# Schematic1.net
KiCad netlist of a schematic drawn in EasyEDA Pro
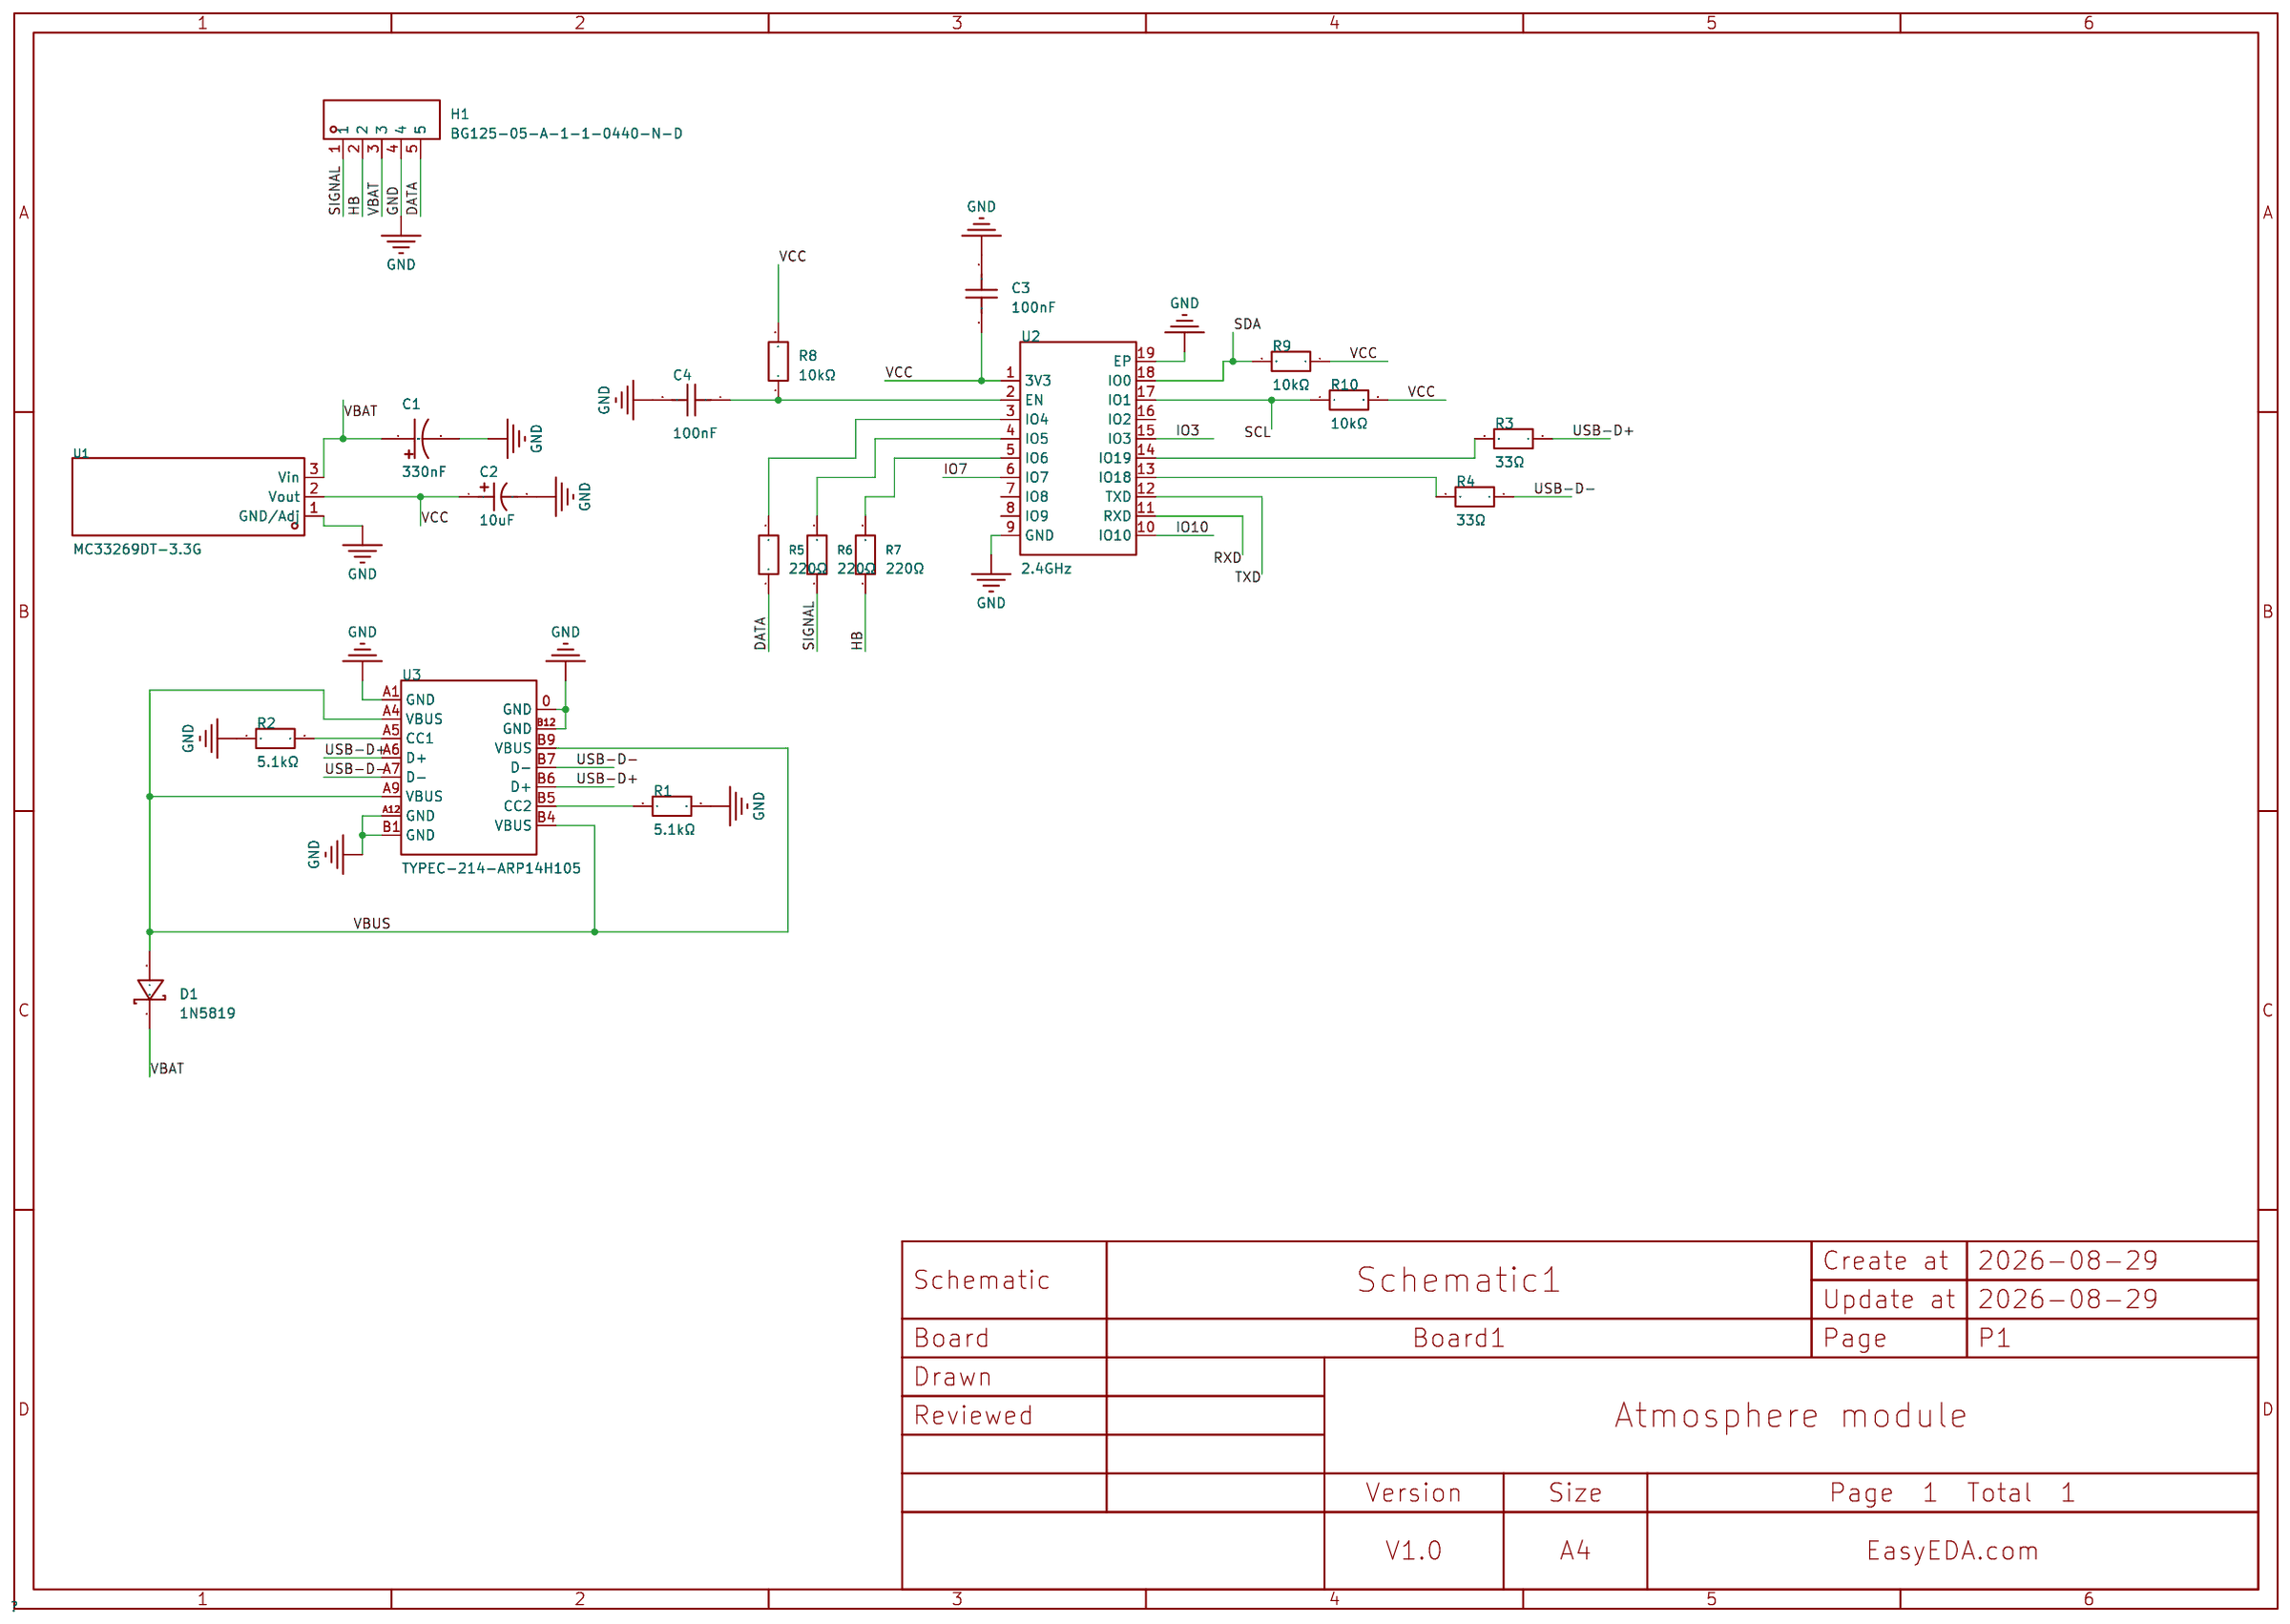
[diagram p0: schematic sheet]

(export (version "E")
  (design (tool "Eeschema 10.0.6"))
  (components
    (comp (ref "C1")
      (value "330nF")
      (footprint "easyedapro:CAP-SMD_L3.2-W1.6")
      (fields (field (name "Manufacturer Part") "T491A334K035AT") (field (name "Manufacturer") "KEMET(基美)"))
      (libsource (lib "easyedapro") (part "T491A334K035AT"))
    )
    (comp (ref "C2")
      (value "10uF")
      (footprint "easyedapro:CASE-A_3216")
      (fields
        (field (name "Manufacturer Part") "T491A106K010AT")
        (field (name "Manufacturer") "KEMET(基美)")
        (field (name "Tolerance") "±10%")
      )
      (libsource (lib "easyedapro") (part "T491A106K010AT_C1508940"))
    )
    (comp (ref "C3")
      (value "100nF")
      (footprint "easyedapro:C0805")
      (fields
        (field (name "Manufacturer Part") "GRM21B7U1A104JA01L")
        (field (name "Manufacturer") "muRata(村田)")
        (field (name "Tolerance") "±5%")
      )
      (libsource (lib "easyedapro") (part "GRM21B7U1A104JA01L"))
    )
    (comp (ref "C4")
      (value "100nF")
      (footprint "easyedapro:C0805")
      (fields
        (field (name "Manufacturer Part") "GRM21B7U1A104JA01L")
        (field (name "Manufacturer") "muRata(村田)")
      )
      (libsource (lib "easyedapro") (part "GRM21B7U1A104JA01L"))
    )
    (comp (ref "D1")
      (value "1N5819")
      (footprint "easyedapro:SMA_L4.4-W2.6-LS5.0-RD")
      (fields (field (name "Manufacturer") "KEXIN(科信)"))
      (libsource (lib "easyedapro") (part "1N5819_C437199"))
    )
    (comp (ref "H1")
      (value "BG125-05-A-1-1-0440-N-D")
      (footprint "easyedapro:HDR-SMD_5P-P2.54-V-F-LS4.4")
      (fields (field (name "Manufacturer") "GCT"))
      (libsource (lib "easyedapro") (part "BG125-05-A-1-1-0440-N-D"))
    )
    (comp (ref "R1")
      (value "5.1kΩ")
      (footprint "easyedapro:R0805")
      (fields
        (field (name "Manufacturer Part") "ERA6AEB512V")
        (field (name "Manufacturer") "PANASONIC(松下)")
        (field (name "Tolerance") "±0.1%")
      )
      (libsource (lib "easyedapro") (part "ERA6AEB512V"))
    )
    (comp (ref "R2")
      (value "5.1kΩ")
      (footprint "easyedapro:R0805")
      (fields
        (field (name "Manufacturer Part") "ERA6AEB512V")
        (field (name "Manufacturer") "PANASONIC(松下)")
        (field (name "Tolerance") "±0.1%")
      )
      (libsource (lib "easyedapro") (part "ERA6AEB512V"))
    )
    (comp (ref "R3")
      (value "33Ω")
      (footprint "easyedapro:R0805")
      (fields
        (field (name "Manufacturer Part") "ERJ6ENF33R0V")
        (field (name "Manufacturer") "PANASONIC(松下)")
        (field (name "Tolerance") "±1%")
      )
      (libsource (lib "easyedapro") (part "ERJ6ENF33R0V"))
    )
    (comp (ref "R4")
      (value "33Ω")
      (footprint "easyedapro:R0805")
      (fields
        (field (name "Manufacturer Part") "ERJ6ENF33R0V")
        (field (name "Manufacturer") "PANASONIC(松下)")
        (field (name "Tolerance") "±1%")
      )
      (libsource (lib "easyedapro") (part "ERJ6ENF33R0V"))
    )
    (comp (ref "R5")
      (value "220Ω")
      (footprint "easyedapro:R0805")
      (fields (field (name "Manufacturer Part") "ERA6AEB221V") (field (name "Manufacturer") "PANASONIC(松下)"))
      (libsource (lib "easyedapro") (part "ERA6AEB221V"))
    )
    (comp (ref "R6")
      (value "220Ω")
      (footprint "easyedapro:R0805")
      (fields (field (name "Manufacturer Part") "ERA6AEB221V") (field (name "Manufacturer") "PANASONIC(松下)"))
      (libsource (lib "easyedapro") (part "ERA6AEB221V"))
    )
    (comp (ref "R7")
      (value "220Ω")
      (footprint "easyedapro:R0805")
      (fields (field (name "Manufacturer Part") "ERA6AEB221V") (field (name "Manufacturer") "PANASONIC(松下)"))
      (libsource (lib "easyedapro") (part "ERA6AEB221V"))
    )
    (comp (ref "R8")
      (value "10kΩ")
      (footprint "easyedapro:R0805")
      (fields (field (name "Manufacturer Part") "ERJP06F1002V") (field (name "Manufacturer") "PANASONIC(松下)"))
      (libsource (lib "easyedapro") (part "ERJP06F1002V"))
    )
    (comp (ref "R9")
      (value "10kΩ")
      (footprint "easyedapro:R0805")
      (fields (field (name "Manufacturer Part") "ERJP06F1002V") (field (name "Manufacturer") "PANASONIC(松下)"))
      (libsource (lib "easyedapro") (part "ERJP06F1002V"))
    )
    (comp (ref "R10")
      (value "10kΩ")
      (footprint "easyedapro:R0805")
      (fields (field (name "Manufacturer Part") "ERJP06F1002V") (field (name "Manufacturer") "PANASONIC(松下)"))
      (libsource (lib "easyedapro") (part "ERJP06F1002V"))
    )
    (comp (ref "U1")
      (value "MC33269DT-3.3G")
      (footprint "easyedapro:TO-252-2_L6.6-W6.1-P4.57-LS9.9-BR-CW")
      (fields (field (name "Manufacturer") "onsemi(安森美)"))
      (libsource (lib "easyedapro") (part "MC33269DT-3.3G"))
    )
    (comp (ref "U2")
      (value "2.4GHz")
      (footprint "easyedapro:BULETM-SMD_ESPRESSIF_ESP32-C3-WROOM-02-N4-4MB")
      (fields
        (field (name "Manufacturer Part") "ESP32-C3-WROOM-02-N4")
        (field (name "Manufacturer") "ESPRESSIF(乐鑫)")
      )
      (libsource (lib "easyedapro") (part "ESP32-C3-WROOM-02-N4(4MB)"))
    )
    (comp (ref "U3")
      (value "TYPEC-214-ARP14H105")
      (footprint "easyedapro:USB-TYPE-C-TH_TYPEC-214-ARP14H105")
      (fields (field (name "Manufacturer") "XUNPU(讯普)"))
      (libsource (lib "easyedapro") (part "TYPEC-214-ARP14H105"))
    )
  )
  (nets
    (net (code "1") (name "/DATA") (class "Default")
      (node (ref "H1") (pin "5") (pinfunction "5_5") (pintype "unspecified"))
      (node (ref "R5") (pin "1") (pinfunction "1_1") (pintype "input"))
    )
    (net (code "2") (name "/HB") (class "Default")
      (node (ref "H1") (pin "2") (pinfunction "2_2") (pintype "unspecified"))
      (node (ref "R7") (pin "1") (pinfunction "1_1") (pintype "input"))
    )
    (net (code "3") (name "/IO3") (class "Default")
      (node (ref "U2") (pin "15") (pinfunction "IO3_15") (pintype "unspecified"))
    )
    (net (code "4") (name "/IO7") (class "Default")
      (node (ref "U2") (pin "6") (pinfunction "IO7_6") (pintype "unspecified"))
    )
    (net (code "5") (name "/IO10") (class "Default")
      (node (ref "U2") (pin "10") (pinfunction "IO10_10") (pintype "unspecified"))
    )
    (net (code "6") (name "/RXD") (class "Default")
      (node (ref "U2") (pin "11") (pinfunction "RXD_11") (pintype "unspecified"))
    )
    (net (code "7") (name "/SCL") (class "Default")
      (node (ref "R10") (pin "1") (pinfunction "1_1") (pintype "unspecified"))
      (node (ref "U2") (pin "17") (pinfunction "IO1_17") (pintype "unspecified"))
    )
    (net (code "8") (name "/SDA") (class "Default")
      (node (ref "R9") (pin "2") (pinfunction "2_2") (pintype "unspecified"))
      (node (ref "U2") (pin "18") (pinfunction "IO0_18") (pintype "unspecified"))
    )
    (net (code "9") (name "/SIGNAL") (class "Default")
      (node (ref "H1") (pin "1") (pinfunction "1_1") (pintype "unspecified"))
      (node (ref "R6") (pin "1") (pinfunction "1_1") (pintype "input"))
    )
    (net (code "10") (name "/TXD") (class "Default")
      (node (ref "U2") (pin "12") (pinfunction "TXD_12") (pintype "unspecified"))
    )
    (net (code "11") (name "/USB-D+") (class "Default")
      (node (ref "R3") (pin "1") (pinfunction "1_1") (pintype "unspecified"))
      (node (ref "U3") (pin "A6") (pinfunction "D+_A6") (pintype "unspecified"))
      (node (ref "U3") (pin "B6") (pinfunction "D+_B6") (pintype "unspecified"))
    )
    (net (code "12") (name "/USB-D-") (class "Default")
      (node (ref "R4") (pin "1") (pinfunction "1_1") (pintype "unspecified"))
      (node (ref "U3") (pin "A7") (pinfunction "D-_A7") (pintype "unspecified"))
      (node (ref "U3") (pin "B7") (pinfunction "D-_B7") (pintype "unspecified"))
    )
    (net (code "13") (name "/VBAT") (class "Default")
      (node (ref "C1") (pin "1") (pinfunction "1_1") (pintype "unspecified"))
      (node (ref "D1") (pin "1") (pinfunction "C_1") (pintype "unspecified"))
      (node (ref "H1") (pin "3") (pinfunction "3_3") (pintype "unspecified"))
      (node (ref "U1") (pin "3") (pinfunction "Vin_3") (pintype "input"))
    )
    (net (code "14") (name "/VBUS") (class "Default")
      (node (ref "D1") (pin "2") (pinfunction "A_2") (pintype "unspecified"))
      (node (ref "U3") (pin "A4") (pinfunction "VBUS_A4") (pintype "unspecified"))
      (node (ref "U3") (pin "A9") (pinfunction "VBUS_A9") (pintype "unspecified"))
      (node (ref "U3") (pin "B4") (pinfunction "VBUS_B4") (pintype "unspecified"))
      (node (ref "U3") (pin "B9") (pinfunction "VBUS_B9") (pintype "unspecified"))
    )
    (net (code "15") (name "/VCC") (class "Default")
      (node (ref "C2") (pin "1") (pinfunction "1_1") (pintype "input"))
      (node (ref "C3") (pin "2") (pinfunction "2_2") (pintype "input"))
      (node (ref "R10") (pin "2") (pinfunction "2_2") (pintype "unspecified"))
      (node (ref "R8") (pin "2") (pinfunction "2_2") (pintype "unspecified"))
      (node (ref "R9") (pin "1") (pinfunction "1_1") (pintype "unspecified"))
      (node (ref "U1") (pin "2") (pinfunction "Vout_2") (pintype "input"))
      (node (ref "U2") (pin "1") (pinfunction "3V3_1") (pintype "unspecified"))
    )
    (net (code "16") (name "GND") (class "Default")
      (node (ref "C1") (pin "2") (pinfunction "2_2") (pintype "unspecified"))
      (node (ref "C2") (pin "2") (pinfunction "2_2") (pintype "input"))
      (node (ref "C3") (pin "1") (pinfunction "1_1") (pintype "input"))
      (node (ref "C4") (pin "2") (pinfunction "2_2") (pintype "input"))
      (node (ref "H1") (pin "4") (pinfunction "4_4") (pintype "unspecified"))
      (node (ref "R1") (pin "2") (pinfunction "2_2") (pintype "unspecified"))
      (node (ref "R2") (pin "1") (pinfunction "1_1") (pintype "unspecified"))
      (node (ref "U1") (pin "1") (pinfunction "GND/Adj_1") (pintype "input"))
      (node (ref "U2") (pin "19") (pinfunction "EP_19") (pintype "unspecified"))
      (node (ref "U2") (pin "9") (pinfunction "GND_9") (pintype "unspecified"))
      (node (ref "U3") (pin "0") (pinfunction "GND_0") (pintype "unspecified"))
      (node (ref "U3") (pin "A1") (pinfunction "GND_A1") (pintype "unspecified"))
      (node (ref "U3") (pin "A12") (pinfunction "GND_A12") (pintype "unspecified"))
      (node (ref "U3") (pin "B1") (pinfunction "GND_B1") (pintype "unspecified"))
      (node (ref "U3") (pin "B12") (pinfunction "GND_B12") (pintype "unspecified"))
    )
    (net (code "17") (name "Net-(U2-EN)") (class "Default")
      (node (ref "C4") (pin "1") (pinfunction "1_1") (pintype "input"))
      (node (ref "R8") (pin "1") (pinfunction "1_1") (pintype "unspecified"))
      (node (ref "U2") (pin "2") (pinfunction "EN_2") (pintype "unspecified"))
    )
    (net (code "18") (name "Net-(U2-IO4)") (class "Default")
      (node (ref "R5") (pin "2") (pinfunction "2_2") (pintype "input"))
      (node (ref "U2") (pin "3") (pinfunction "IO4_3") (pintype "unspecified"))
    )
    (net (code "19") (name "Net-(U2-IO5)") (class "Default")
      (node (ref "R6") (pin "2") (pinfunction "2_2") (pintype "input"))
      (node (ref "U2") (pin "4") (pinfunction "IO5_4") (pintype "unspecified"))
    )
    (net (code "20") (name "Net-(U2-IO6)") (class "Default")
      (node (ref "R7") (pin "2") (pinfunction "2_2") (pintype "input"))
      (node (ref "U2") (pin "5") (pinfunction "IO6_5") (pintype "unspecified"))
    )
    (net (code "21") (name "Net-(U2-IO18)") (class "Default")
      (node (ref "R4") (pin "2") (pinfunction "2_2") (pintype "unspecified"))
      (node (ref "U2") (pin "13") (pinfunction "IO18_13") (pintype "unspecified"))
    )
    (net (code "22") (name "Net-(U2-IO19)") (class "Default")
      (node (ref "R3") (pin "2") (pinfunction "2_2") (pintype "unspecified"))
      (node (ref "U2") (pin "14") (pinfunction "IO19_14") (pintype "unspecified"))
    )
    (net (code "23") (name "Net-(U3-CC1)") (class "Default")
      (node (ref "R2") (pin "2") (pinfunction "2_2") (pintype "unspecified"))
      (node (ref "U3") (pin "A5") (pinfunction "CC1_A5") (pintype "unspecified"))
    )
    (net (code "24") (name "Net-(U3-CC2)") (class "Default")
      (node (ref "R1") (pin "1") (pinfunction "1_1") (pintype "unspecified"))
      (node (ref "U3") (pin "B5") (pinfunction "CC2_B5") (pintype "unspecified"))
    )
    (net (code "25") (name "unconnected-(U2-IO2-Pad16)") (class "Default")
      (node (ref "U2") (pin "16") (pinfunction "IO2_16") (pintype "unspecified"))
    )
    (net (code "26") (name "unconnected-(U2-IO8-Pad7)") (class "Default")
      (node (ref "U2") (pin "7") (pinfunction "IO8_7") (pintype "unspecified"))
    )
    (net (code "27") (name "unconnected-(U2-IO9-Pad8)") (class "Default")
      (node (ref "U2") (pin "8") (pinfunction "IO9_8") (pintype "unspecified"))
    )
  )
)
